# ece411-t10-ChargerBase.net
KiCad netlist of a schematic drawn in EAGLE
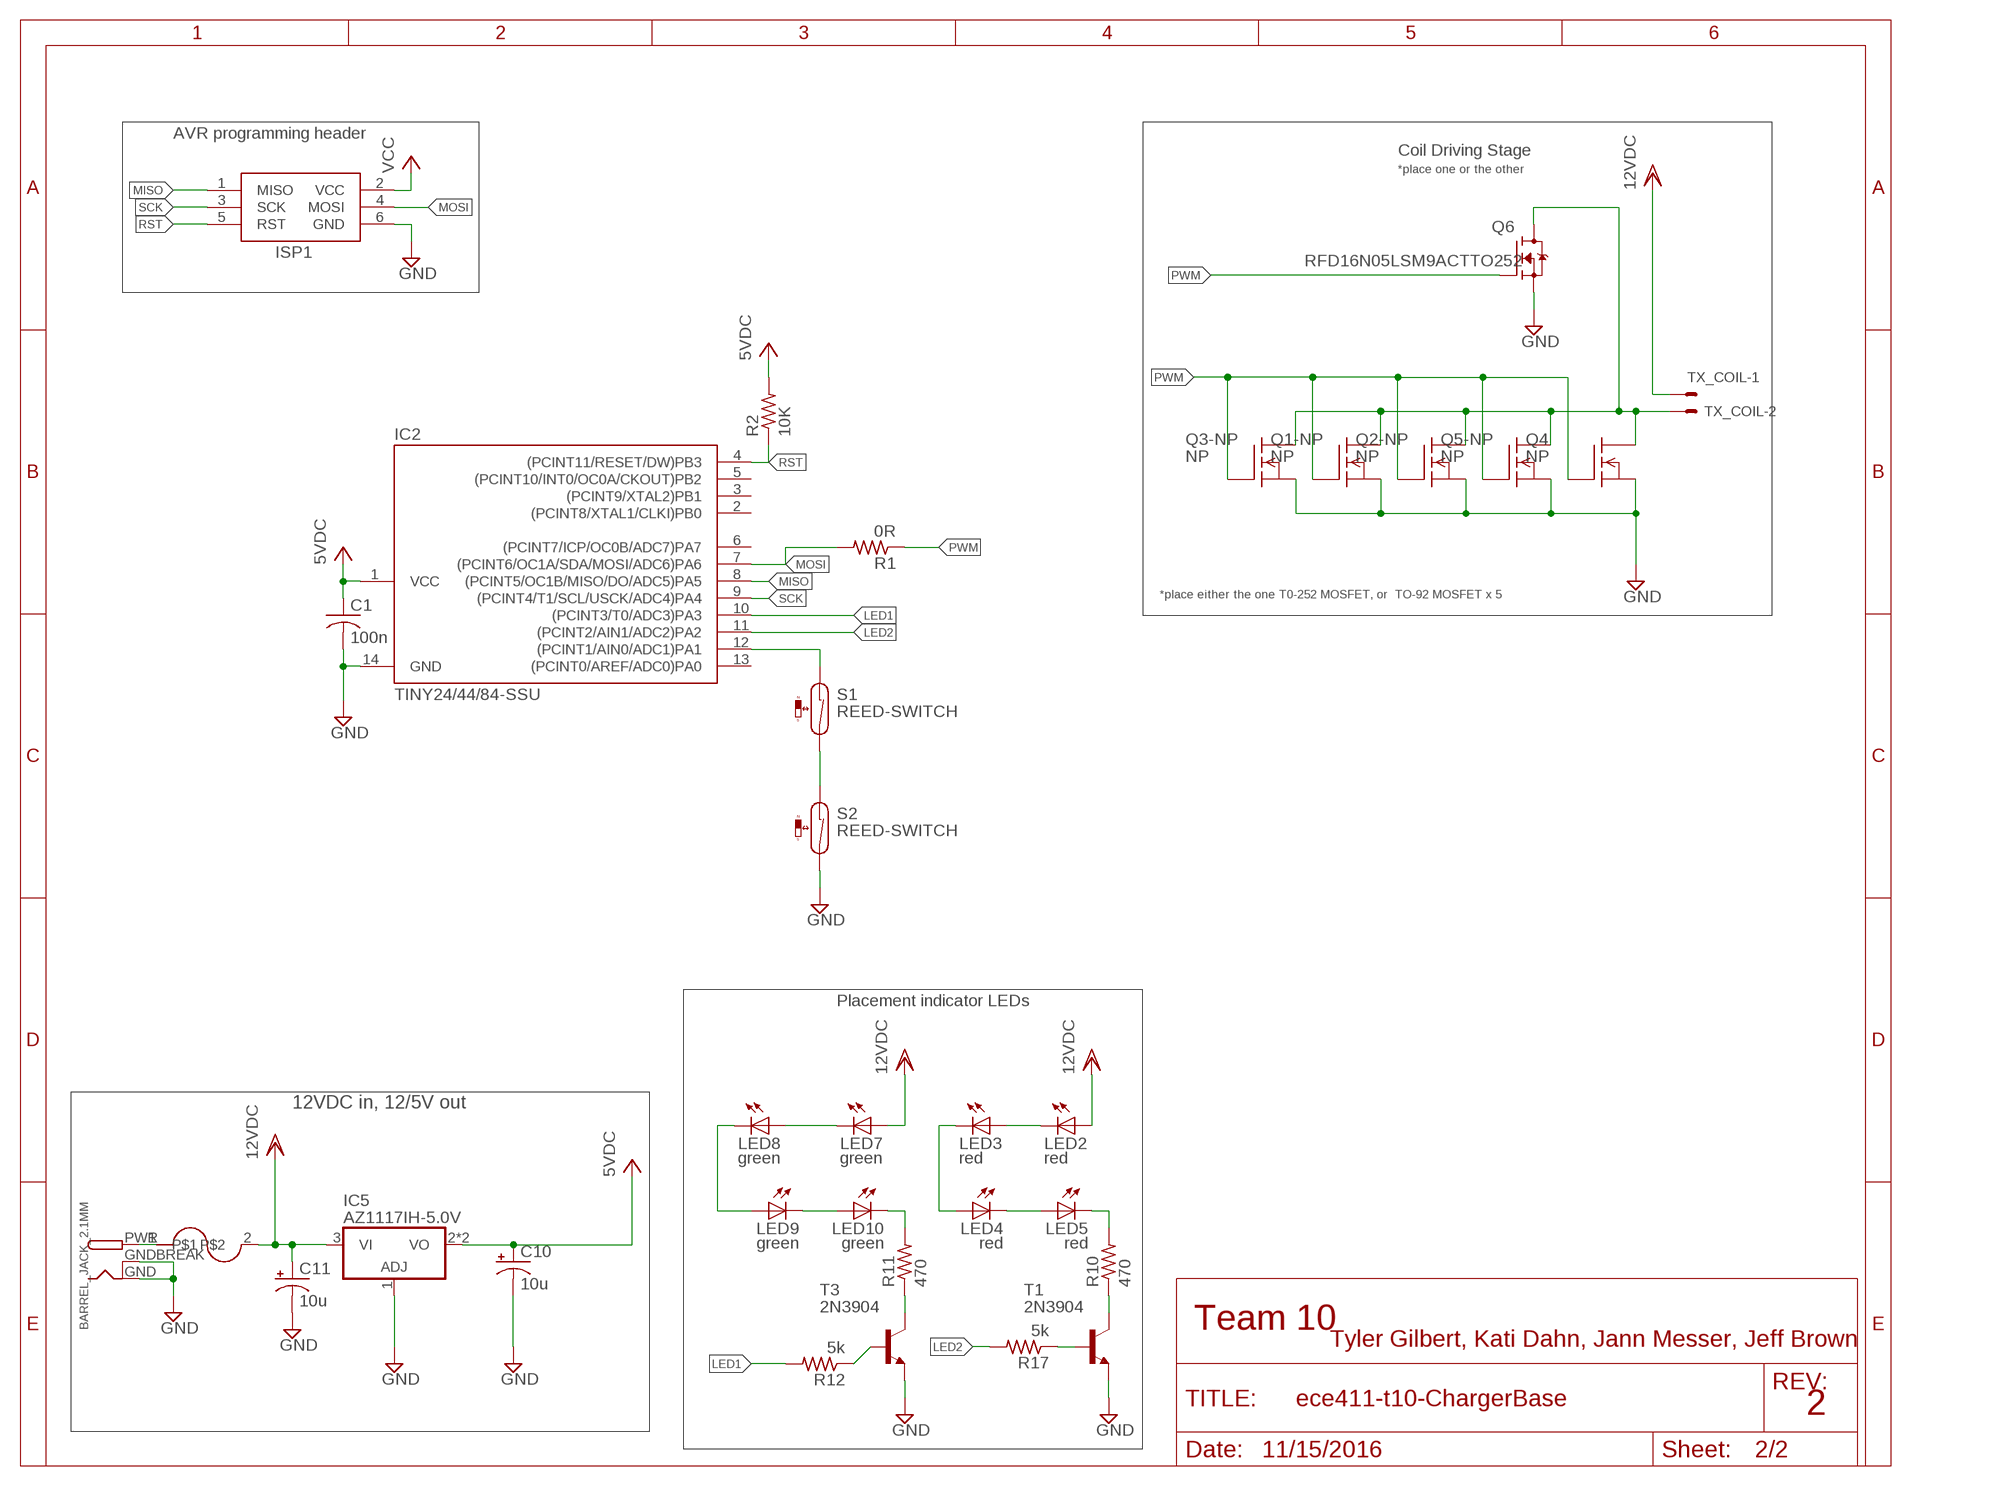
[diagram p0: schematic, sheet 1]

(export (version "E")
  (design (tool "Eeschema 10.0.6"))
  (components
    (comp (ref "BARREL_JACK_2.1MM")
      (value "DCBARRELPTH")
      (footprint "eagle-import:DCJACK_2MM_PTH")
      (libsource (lib "eagle-import") (part "DCBARRELPTH"))
    )
    (comp (ref "C1")
      (value "100n")
      (footprint "eagle-import:C0805")
      (libsource (lib "eagle-import") (part "C-USC0805"))
    )
    (comp (ref "C10")
      (value "10u")
      (footprint "eagle-import:E2-5")
      (libsource (lib "eagle-import") (part "CPOL-USE2-5"))
    )
    (comp (ref "C11")
      (value "10u")
      (footprint "eagle-import:E2-5")
      (libsource (lib "eagle-import") (part "CPOL-USE2-5"))
    )
    (comp (ref "IC2")
      (value "TINY24/44/84-SSU")
      (footprint "eagle-import:SOIC14")
      (libsource (lib "eagle-import") (part "TINY24/44/84-SSU"))
    )
    (comp (ref "IC5")
      (value "AZ1117IH-5.0V")
      (footprint "eagle-import:SOT223")
      (libsource (lib "eagle-import") (part "317EMP"))
    )
    (comp (ref "ISP1")
      (value "AVRISP-6")
      (footprint "eagle-import:AVRISP")
      (libsource (lib "eagle-import") (part "AVRISP-6"))
    )
    (comp (ref "LED2")
      (value "red")
      (footprint "eagle-import:CHIPLED_0805")
      (libsource (lib "eagle-import") (part "LEDCHIPLED_0805"))
    )
    (comp (ref "LED3")
      (value "red")
      (footprint "eagle-import:CHIPLED_0805")
      (libsource (lib "eagle-import") (part "LEDCHIPLED_0805"))
    )
    (comp (ref "LED4")
      (value "red")
      (footprint "eagle-import:CHIPLED_0805")
      (libsource (lib "eagle-import") (part "LEDCHIPLED_0805"))
    )
    (comp (ref "LED5")
      (value "red")
      (footprint "eagle-import:CHIPLED_0805")
      (libsource (lib "eagle-import") (part "LEDCHIPLED_0805"))
    )
    (comp (ref "LED7")
      (value "green")
      (footprint "eagle-import:CHIPLED_0805")
      (libsource (lib "eagle-import") (part "LEDCHIPLED_0805"))
    )
    (comp (ref "LED8")
      (value "green")
      (footprint "eagle-import:CHIPLED_0805")
      (libsource (lib "eagle-import") (part "LEDCHIPLED_0805"))
    )
    (comp (ref "LED9")
      (value "green")
      (footprint "eagle-import:CHIPLED_0805")
      (libsource (lib "eagle-import") (part "LEDCHIPLED_0805"))
    )
    (comp (ref "LED10")
      (value "green")
      (footprint "eagle-import:CHIPLED_0805")
      (libsource (lib "eagle-import") (part "LEDCHIPLED_0805"))
    )
    (comp (ref "Q1-NP")
      (value "NP")
      (footprint "eagle-import:TO-92")
      (libsource (lib "eagle-import") (part "TN0602N3"))
    )
    (comp (ref "Q2-NP")
      (value "NP")
      (footprint "eagle-import:TO-92")
      (libsource (lib "eagle-import") (part "TN0602N3"))
    )
    (comp (ref "Q3-NP")
      (value "NP")
      (footprint "eagle-import:TO-92")
      (libsource (lib "eagle-import") (part "TN0602N3"))
    )
    (comp (ref "Q4")
      (value "NP")
      (footprint "eagle-import:TO-92")
      (libsource (lib "eagle-import") (part "TN0602N3"))
    )
    (comp (ref "Q5-NP")
      (value "NP")
      (footprint "eagle-import:TO-92")
      (libsource (lib "eagle-import") (part "TN0602N3"))
    )
    (comp (ref "Q6")
      (value "RFD16N05LSM9ACTTO252")
      (footprint "eagle-import:TO252")
      (libsource (lib "eagle-import") (part "RFD16N05LSM9ACTTO252"))
    )
    (comp (ref "R1")
      (value "0R")
      (footprint "eagle-import:R0805")
      (libsource (lib "eagle-import") (part "R-US_R0805"))
    )
    (comp (ref "R2")
      (value "10K")
      (footprint "eagle-import:R0805")
      (libsource (lib "eagle-import") (part "R-US_R0805"))
    )
    (comp (ref "R10")
      (value "470")
      (footprint "eagle-import:R0805")
      (libsource (lib "eagle-import") (part "R-US_R0805"))
    )
    (comp (ref "R11")
      (value "470")
      (footprint "eagle-import:R0805")
      (libsource (lib "eagle-import") (part "R-US_R0805"))
    )
    (comp (ref "R12")
      (value "5k")
      (footprint "eagle-import:R0805")
      (libsource (lib "eagle-import") (part "R-US_R0805"))
    )
    (comp (ref "R17")
      (value "5k")
      (footprint "eagle-import:R0805")
      (libsource (lib "eagle-import") (part "R-US_R0805"))
    )
    (comp (ref "S1")
      (value "REED-SWITCH")
      (footprint "eagle-import:MK6-6")
      (libsource (lib "eagle-import") (part "REED-SWITCH-MK6-6"))
    )
    (comp (ref "S2")
      (value "REED-SWITCH")
      (footprint "eagle-import:MK6-6")
      (libsource (lib "eagle-import") (part "REED-SWITCH-MK6-6"))
    )
    (comp (ref "T1")
      (value "2N3904")
      (footprint "eagle-import:TO92")
      (libsource (lib "eagle-import") (part "2N3904"))
    )
    (comp (ref "T3")
      (value "2N3904")
      (footprint "eagle-import:TO92")
      (libsource (lib "eagle-import") (part "2N3904"))
    )
    (comp (ref "TX_COIL")
      (value "22-23-2021")
      (footprint "eagle-import:22-23-2021")
      (fields (field (name "MF") "MOLEX"))
      (libsource (lib "eagle-import") (part "22-23-2021"))
    )
    (comp (ref "U$1")
      (value "LITTLEFUSE")
      (footprint "eagle-import:LITTLEFUSE")
      (libsource (lib "eagle-import") (part "LITTLEFUSE"))
    )
  )
  (nets
    (net (code "1") (name "5VDC") (class "Default")
      (node (ref "C1") (pin "1") (pinfunction "1_1") (pintype "passive"))
      (node (ref "C10") (pin "+") (pinfunction "+_+") (pintype "passive"))
      (node (ref "IC2") (pin "1") (pinfunction "VCC_1") (pintype "power_in"))
      (node (ref "IC5") (pin "2") (pinfunction "VO_2") (pintype "passive"))
      (node (ref "IC5") (pin "4") (pinfunction "VO_4") (pintype "passive"))
      (node (ref "ISP1") (pin "2") (pinfunction "VCC_2") (pintype "power_in"))
      (node (ref "R2") (pin "2") (pinfunction "2_2") (pintype "passive"))
    )
    (net (code "2") (name "12VDC") (class "Default")
      (node (ref "C11") (pin "+") (pinfunction "+_+") (pintype "passive"))
      (node (ref "IC5") (pin "3") (pinfunction "VI_3") (pintype "input"))
      (node (ref "LED2") (pin "A") (pinfunction "A_A") (pintype "passive"))
      (node (ref "LED7") (pin "A") (pinfunction "A_A") (pintype "passive"))
      (node (ref "TX_COIL") (pin "1") (pinfunction "S_1") (pintype "passive"))
      (node (ref "U$1") (pin "2") (pinfunction "P$2_2") (pintype "bidirectional"))
    )
    (net (code "3") (name "GND") (class "Default")
      (node (ref "BARREL_JACK_2.1MM") (pin "GND") (pinfunction "GND_GND") (pintype "power_in"))
      (node (ref "BARREL_JACK_2.1MM") (pin "GNDBREAK") (pinfunction "GNDBREAK_GNDBREAK") (pintype "power_in"))
      (node (ref "C1") (pin "2") (pinfunction "2_2") (pintype "passive"))
      (node (ref "C10") (pin "-") (pinfunction "-_-") (pintype "passive"))
      (node (ref "C11") (pin "-") (pinfunction "-_-") (pintype "passive"))
      (node (ref "IC2") (pin "14") (pinfunction "GND_14") (pintype "power_in"))
      (node (ref "IC5") (pin "1") (pinfunction "ADJ_1") (pintype "input"))
      (node (ref "ISP1") (pin "6") (pinfunction "GND_6") (pintype "power_in"))
      (node (ref "Q1-NP") (pin "1") (pinfunction "S_1") (pintype "passive"))
      (node (ref "Q2-NP") (pin "1") (pinfunction "S_1") (pintype "passive"))
      (node (ref "Q3-NP") (pin "1") (pinfunction "S_1") (pintype "passive"))
      (node (ref "Q4") (pin "1") (pinfunction "S_1") (pintype "passive"))
      (node (ref "Q5-NP") (pin "1") (pinfunction "S_1") (pintype "passive"))
      (node (ref "Q6") (pin "2") (pinfunction "S_2") (pintype "passive"))
      (node (ref "S2") (pin "2") (pinfunction "2_2") (pintype "passive"))
      (node (ref "T1") (pin "3") (pinfunction "E_3") (pintype "passive"))
      (node (ref "T3") (pin "3") (pinfunction "E_3") (pintype "passive"))
    )
    (net (code "4") (name "LED1") (class "Default")
      (node (ref "IC2") (pin "10") (pinfunction "(PCINT3/T0/ADC3)PA3_10") (pintype "bidirectional"))
      (node (ref "R12") (pin "2") (pinfunction "2_2") (pintype "passive"))
    )
    (net (code "5") (name "LED2") (class "Default")
      (node (ref "IC2") (pin "11") (pinfunction "(PCINT2/AIN1/ADC2)PA2_11") (pintype "bidirectional"))
      (node (ref "R17") (pin "2") (pinfunction "2_2") (pintype "passive"))
    )
    (net (code "6") (name "MISO") (class "Default")
      (node (ref "IC2") (pin "8") (pinfunction "(PCINT5/OC1B/MISO/DO/ADC5)PA5_8") (pintype "bidirectional"))
      (node (ref "ISP1") (pin "1") (pinfunction "MISO_1") (pintype "input"))
    )
    (net (code "7") (name "MOSI") (class "Default")
      (node (ref "IC2") (pin "7") (pinfunction "(PCINT6/OC1A/SDA/MOSI/ADC6)PA6_7") (pintype "bidirectional"))
      (node (ref "ISP1") (pin "4") (pinfunction "MOSI_4") (pintype "output"))
      (node (ref "R1") (pin "2") (pinfunction "2_2") (pintype "passive"))
    )
    (net (code "8") (name "Net-(IC2-(PCINT1{slash}AIN0{slash}ADC1)PA1)") (class "Default")
      (node (ref "IC2") (pin "12") (pinfunction "(PCINT1/AIN0/ADC1)PA1_12") (pintype "bidirectional"))
      (node (ref "S1") (pin "1") (pinfunction "1_1") (pintype "passive"))
    )
    (net (code "9") (name "Net-(LED2-PadC)") (class "Default")
      (node (ref "LED2") (pin "C") (pinfunction "C_C") (pintype "passive"))
      (node (ref "LED3") (pin "A") (pinfunction "A_A") (pintype "passive"))
    )
    (net (code "10") (name "Net-(LED3-PadC)") (class "Default")
      (node (ref "LED3") (pin "C") (pinfunction "C_C") (pintype "passive"))
      (node (ref "LED4") (pin "A") (pinfunction "A_A") (pintype "passive"))
    )
    (net (code "11") (name "Net-(LED4-PadC)") (class "Default")
      (node (ref "LED4") (pin "C") (pinfunction "C_C") (pintype "passive"))
      (node (ref "LED5") (pin "A") (pinfunction "A_A") (pintype "passive"))
    )
    (net (code "12") (name "Net-(LED5-PadC)") (class "Default")
      (node (ref "LED5") (pin "C") (pinfunction "C_C") (pintype "passive"))
      (node (ref "R10") (pin "2") (pinfunction "2_2") (pintype "passive"))
    )
    (net (code "13") (name "Net-(LED7-PadC)") (class "Default")
      (node (ref "LED7") (pin "C") (pinfunction "C_C") (pintype "passive"))
      (node (ref "LED8") (pin "A") (pinfunction "A_A") (pintype "passive"))
    )
    (net (code "14") (name "Net-(LED8-PadC)") (class "Default")
      (node (ref "LED8") (pin "C") (pinfunction "C_C") (pintype "passive"))
      (node (ref "LED9") (pin "A") (pinfunction "A_A") (pintype "passive"))
    )
    (net (code "15") (name "Net-(LED10-PadA)") (class "Default")
      (node (ref "LED10") (pin "A") (pinfunction "A_A") (pintype "passive"))
      (node (ref "LED9") (pin "C") (pinfunction "C_C") (pintype "passive"))
    )
    (net (code "16") (name "Net-(LED10-PadC)") (class "Default")
      (node (ref "LED10") (pin "C") (pinfunction "C_C") (pintype "passive"))
      (node (ref "R11") (pin "2") (pinfunction "2_2") (pintype "passive"))
    )
    (net (code "17") (name "Net-(Q1-NP-D)") (class "Default")
      (node (ref "Q1-NP") (pin "3") (pinfunction "D_3") (pintype "passive"))
      (node (ref "Q2-NP") (pin "3") (pinfunction "D_3") (pintype "passive"))
      (node (ref "Q3-NP") (pin "3") (pinfunction "D_3") (pintype "passive"))
      (node (ref "Q4") (pin "3") (pinfunction "D_3") (pintype "passive"))
      (node (ref "Q5-NP") (pin "3") (pinfunction "D_3") (pintype "passive"))
      (node (ref "Q6") (pin "3") (pinfunction "D_3") (pintype "passive"))
      (node (ref "TX_COIL") (pin "2") (pinfunction "S_2") (pintype "passive"))
    )
    (net (code "18") (name "Net-(S1-Pad2)") (class "Default")
      (node (ref "S1") (pin "2") (pinfunction "2_2") (pintype "passive"))
      (node (ref "S2") (pin "1") (pinfunction "1_1") (pintype "passive"))
    )
    (net (code "19") (name "Net-(T1-B)") (class "Default")
      (node (ref "R17") (pin "1") (pinfunction "1_1") (pintype "passive"))
      (node (ref "T1") (pin "2") (pinfunction "B_2") (pintype "passive"))
    )
    (net (code "20") (name "Net-(T1-C)") (class "Default")
      (node (ref "R10") (pin "1") (pinfunction "1_1") (pintype "passive"))
      (node (ref "T1") (pin "1") (pinfunction "C_1") (pintype "passive"))
    )
    (net (code "21") (name "Net-(T3-B)") (class "Default")
      (node (ref "R12") (pin "1") (pinfunction "1_1") (pintype "passive"))
      (node (ref "T3") (pin "2") (pinfunction "B_2") (pintype "passive"))
    )
    (net (code "22") (name "Net-(T3-C)") (class "Default")
      (node (ref "R11") (pin "1") (pinfunction "1_1") (pintype "passive"))
      (node (ref "T3") (pin "1") (pinfunction "C_1") (pintype "passive"))
    )
    (net (code "23") (name "Net-(U$1-P$1)") (class "Default")
      (node (ref "BARREL_JACK_2.1MM") (pin "PWR") (pinfunction "PWR_PWR") (pintype "power_in"))
      (node (ref "U$1") (pin "1") (pinfunction "P$1_1") (pintype "bidirectional"))
    )
    (net (code "24") (name "PWM") (class "Default")
      (node (ref "Q1-NP") (pin "2") (pinfunction "G_2") (pintype "passive"))
      (node (ref "Q2-NP") (pin "2") (pinfunction "G_2") (pintype "passive"))
      (node (ref "Q3-NP") (pin "2") (pinfunction "G_2") (pintype "passive"))
      (node (ref "Q4") (pin "2") (pinfunction "G_2") (pintype "passive"))
      (node (ref "Q5-NP") (pin "2") (pinfunction "G_2") (pintype "passive"))
      (node (ref "Q6") (pin "1") (pinfunction "G_1") (pintype "passive"))
      (node (ref "R1") (pin "1") (pinfunction "1_1") (pintype "passive"))
    )
    (net (code "25") (name "RST") (class "Default")
      (node (ref "IC2") (pin "4") (pinfunction "(PCINT11/RESET/DW)PB3_4") (pintype "bidirectional"))
      (node (ref "ISP1") (pin "5") (pinfunction "RST_5") (pintype "output"))
      (node (ref "R2") (pin "1") (pinfunction "1_1") (pintype "passive"))
    )
    (net (code "26") (name "SCK") (class "Default")
      (node (ref "IC2") (pin "9") (pinfunction "(PCINT4/T1/SCL/USCK/ADC4)PA4_9") (pintype "bidirectional"))
      (node (ref "ISP1") (pin "3") (pinfunction "SCK_3") (pintype "output"))
    )
    (net (code "27") (name "unconnected-(IC2-(PCINT0{slash}AREF{slash}ADC0)PA0-Pad13)") (class "Default")
      (node (ref "IC2") (pin "13") (pinfunction "(PCINT0/AREF/ADC0)PA0_13") (pintype "bidirectional"))
    )
    (net (code "28") (name "unconnected-(IC2-(PCINT7{slash}ICP{slash}OC0B{slash}ADC7)PA7-Pad6)") (class "Default")
      (node (ref "IC2") (pin "6") (pinfunction "(PCINT7/ICP/OC0B/ADC7)PA7_6") (pintype "bidirectional"))
    )
    (net (code "29") (name "unconnected-(IC2-(PCINT8{slash}XTAL1{slash}CLKI)PB0-Pad2)") (class "Default")
      (node (ref "IC2") (pin "2") (pinfunction "(PCINT8/XTAL1/CLKI)PB0_2") (pintype "bidirectional"))
    )
    (net (code "30") (name "unconnected-(IC2-(PCINT9{slash}XTAL2)PB1-Pad3)") (class "Default")
      (node (ref "IC2") (pin "3") (pinfunction "(PCINT9/XTAL2)PB1_3") (pintype "bidirectional"))
    )
    (net (code "31") (name "unconnected-(IC2-(PCINT10{slash}INT0{slash}OC0A{slash}CKOUT)PB2-Pad5)") (class "Default")
      (node (ref "IC2") (pin "5") (pinfunction "(PCINT10/INT0/OC0A/CKOUT)PB2_5") (pintype "bidirectional"))
    )
  )
)
